# OpenSegment-v13.net
KiCad netlist of a schematic drawn in EAGLE
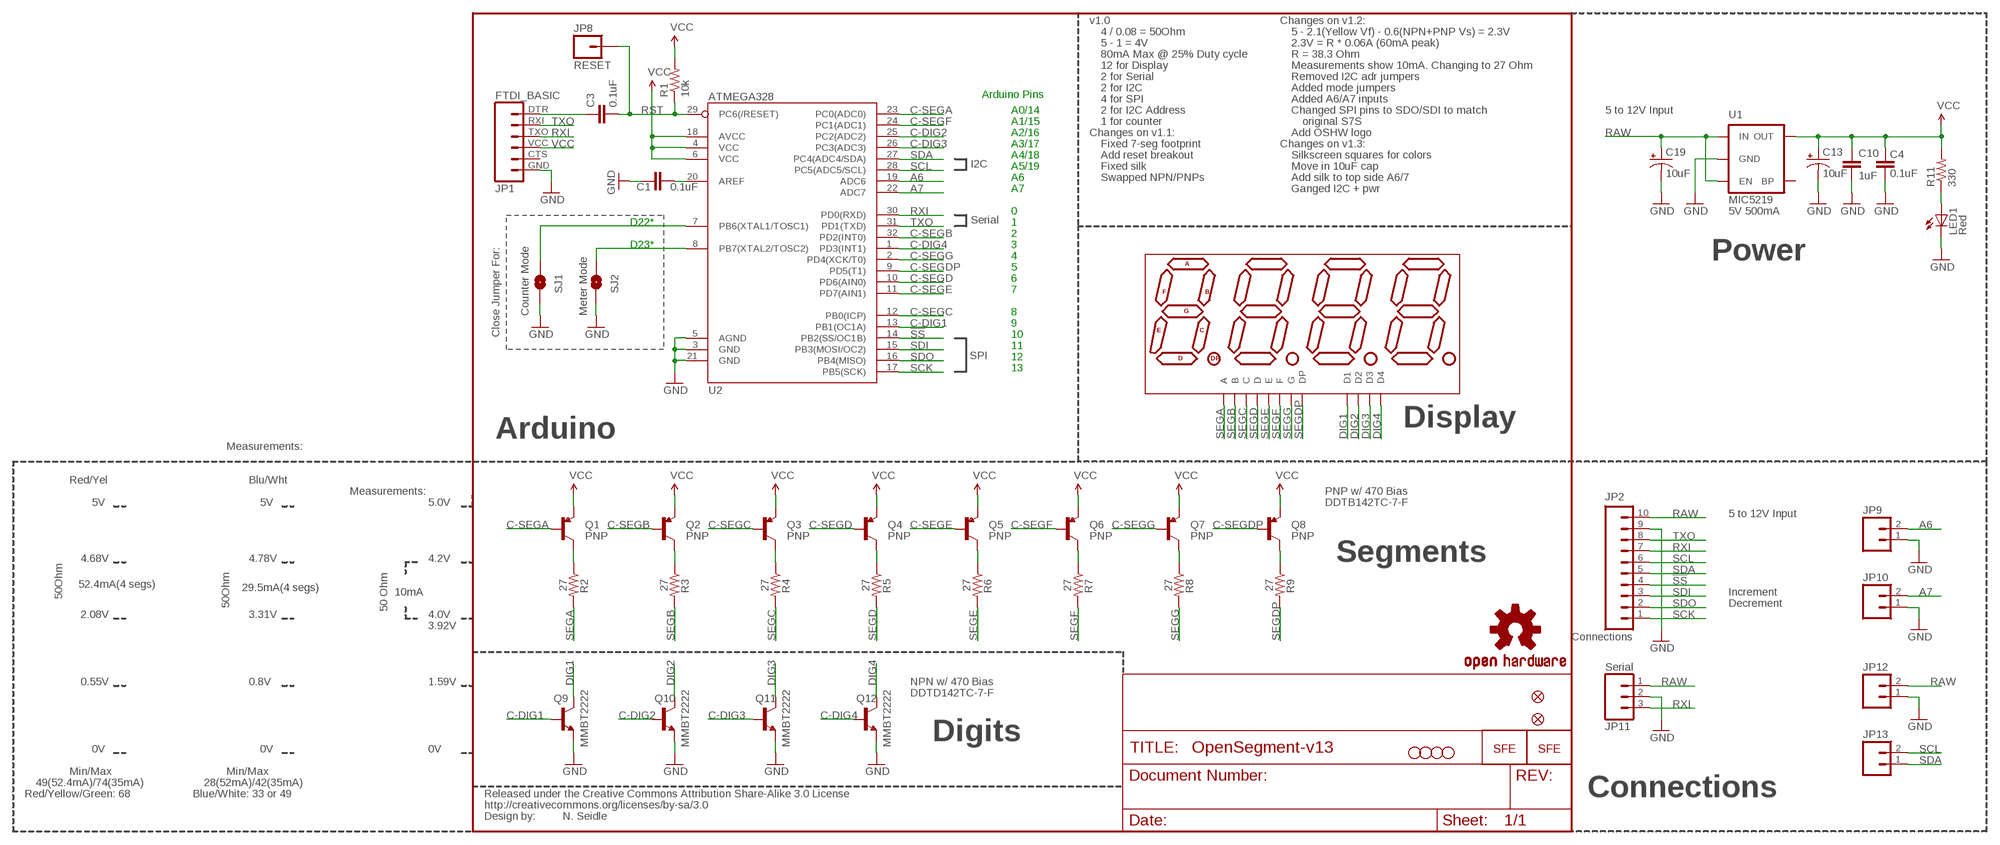
[diagram p0: schematic, sheet 1]

(export (version "E")
  (design (tool "Eeschema 10.0.6"))
  (components
    (comp (ref "C1")
      (value "0.1uF")
      (footprint "eagle-import:0402-CAP")
      (libsource (lib "eagle-import") (part "CAP0402-CAP"))
    )
    (comp (ref "C3")
      (value "0.1uF")
      (footprint "eagle-import:0402-CAP")
      (libsource (lib "eagle-import") (part "CAP0402-CAP"))
    )
    (comp (ref "C4")
      (value "0.1uF")
      (footprint "eagle-import:0402-CAP")
      (libsource (lib "eagle-import") (part "CAP0402-CAP"))
    )
    (comp (ref "C10")
      (value "1uF")
      (footprint "eagle-import:0402-CAP")
      (libsource (lib "eagle-import") (part "CAP0402-CAP"))
    )
    (comp (ref "C13")
      (value "10uF")
      (footprint "eagle-import:EIA3216")
      (libsource (lib "eagle-import") (part "CAP_POL1206"))
    )
    (comp (ref "C19")
      (value "10uF")
      (footprint "eagle-import:EIA3216")
      (libsource (lib "eagle-import") (part "CAP_POL1206"))
    )
    (comp (ref "JP1")
      (value "FTDI_BASIC")
      (footprint "eagle-import:FTDI_BASIC")
      (libsource (lib "eagle-import") (part "FTDI_BASICPTH"))
    )
    (comp (ref "JP2")
      (value "Connections")
      (footprint "eagle-import:1X10")
      (libsource (lib "eagle-import") (part "M10{dblquote}"))
    )
    (comp (ref "JP3")
      (value "STAND-OFF")
      (footprint "eagle-import:STAND-OFF")
      (libsource (lib "eagle-import") (part "STAND-OFF"))
    )
    (comp (ref "JP4")
      (value "STAND-OFF")
      (footprint "eagle-import:STAND-OFF")
      (libsource (lib "eagle-import") (part "STAND-OFF"))
    )
    (comp (ref "JP5")
      (value "STAND-OFF")
      (footprint "eagle-import:STAND-OFF")
      (libsource (lib "eagle-import") (part "STAND-OFF"))
    )
    (comp (ref "JP6")
      (value "STAND-OFF")
      (footprint "eagle-import:STAND-OFF")
      (libsource (lib "eagle-import") (part "STAND-OFF"))
    )
    (comp (ref "JP7")
      (value "FIDUCIALUFIDUCIAL")
      (footprint "eagle-import:MICRO-FIDUCIAL")
      (libsource (lib "eagle-import") (part "FIDUCIALUFIDUCIAL"))
    )
    (comp (ref "JP8")
      (value "RESET")
      (footprint "eagle-import:1X01")
      (libsource (lib "eagle-import") (part "M01PTH"))
    )
    (comp (ref "JP9")
      (value "M02PTH")
      (footprint "eagle-import:1X02")
      (libsource (lib "eagle-import") (part "M02PTH"))
    )
    (comp (ref "JP10")
      (value "M02PTH")
      (footprint "eagle-import:1X02")
      (libsource (lib "eagle-import") (part "M02PTH"))
    )
    (comp (ref "JP11")
      (value "Serial")
      (footprint "eagle-import:JST-3-PTH")
      (libsource (lib "eagle-import") (part "M03JST-PTH"))
    )
    (comp (ref "JP12")
      (value "M02PTH")
      (footprint "eagle-import:1X02")
      (libsource (lib "eagle-import") (part "M02PTH"))
    )
    (comp (ref "JP13")
      (value "M02PTH")
      (footprint "eagle-import:1X02")
      (libsource (lib "eagle-import") (part "M02PTH"))
    )
    (comp (ref "JP14")
      (value "FIDUCIALUFIDUCIAL")
      (footprint "eagle-import:MICRO-FIDUCIAL")
      (libsource (lib "eagle-import") (part "FIDUCIALUFIDUCIAL"))
    )
    (comp (ref "LED1")
      (value "Red")
      (footprint "eagle-import:LED-0603")
      (libsource (lib "eagle-import") (part "LED0603"))
    )
    (comp (ref "Q1")
      (value "PNP")
      (footprint "eagle-import:SOT23-3")
      (libsource (lib "eagle-import") (part "TRANSISTOR_PNPSMD"))
    )
    (comp (ref "Q2")
      (value "PNP")
      (footprint "eagle-import:SOT23-3")
      (libsource (lib "eagle-import") (part "TRANSISTOR_PNPSMD"))
    )
    (comp (ref "Q3")
      (value "PNP")
      (footprint "eagle-import:SOT23-3")
      (libsource (lib "eagle-import") (part "TRANSISTOR_PNPSMD"))
    )
    (comp (ref "Q4")
      (value "PNP")
      (footprint "eagle-import:SOT23-3")
      (libsource (lib "eagle-import") (part "TRANSISTOR_PNPSMD"))
    )
    (comp (ref "Q5")
      (value "PNP")
      (footprint "eagle-import:SOT23-3")
      (libsource (lib "eagle-import") (part "TRANSISTOR_PNPSMD"))
    )
    (comp (ref "Q6")
      (value "PNP")
      (footprint "eagle-import:SOT23-3")
      (libsource (lib "eagle-import") (part "TRANSISTOR_PNPSMD"))
    )
    (comp (ref "Q7")
      (value "PNP")
      (footprint "eagle-import:SOT23-3")
      (libsource (lib "eagle-import") (part "TRANSISTOR_PNPSMD"))
    )
    (comp (ref "Q8")
      (value "PNP")
      (footprint "eagle-import:SOT23-3")
      (libsource (lib "eagle-import") (part "TRANSISTOR_PNPSMD"))
    )
    (comp (ref "Q9")
      (value "MMBT2222")
      (footprint "eagle-import:SOT23-3")
      (libsource (lib "eagle-import") (part "TRANSISTOR_NPNSOT23-3"))
    )
    (comp (ref "Q10")
      (value "MMBT2222")
      (footprint "eagle-import:SOT23-3")
      (libsource (lib "eagle-import") (part "TRANSISTOR_NPNSOT23-3"))
    )
    (comp (ref "Q11")
      (value "MMBT2222")
      (footprint "eagle-import:SOT23-3")
      (libsource (lib "eagle-import") (part "TRANSISTOR_NPNSOT23-3"))
    )
    (comp (ref "Q12")
      (value "MMBT2222")
      (footprint "eagle-import:SOT23-3")
      (libsource (lib "eagle-import") (part "TRANSISTOR_NPNSOT23-3"))
    )
    (comp (ref "R1")
      (value "10k")
      (footprint "eagle-import:0402-RES")
      (libsource (lib "eagle-import") (part "RESISTOR0402-RES"))
    )
    (comp (ref "R2")
      (value "27")
      (footprint "eagle-import:0402-RES")
      (libsource (lib "eagle-import") (part "RESISTOR0402-RES"))
    )
    (comp (ref "R3")
      (value "27")
      (footprint "eagle-import:0402-RES")
      (libsource (lib "eagle-import") (part "RESISTOR0402-RES"))
    )
    (comp (ref "R4")
      (value "27")
      (footprint "eagle-import:0402-RES")
      (libsource (lib "eagle-import") (part "RESISTOR0402-RES"))
    )
    (comp (ref "R5")
      (value "27")
      (footprint "eagle-import:0402-RES")
      (libsource (lib "eagle-import") (part "RESISTOR0402-RES"))
    )
    (comp (ref "R6")
      (value "27")
      (footprint "eagle-import:0402-RES")
      (libsource (lib "eagle-import") (part "RESISTOR0402-RES"))
    )
    (comp (ref "R7")
      (value "27")
      (footprint "eagle-import:0402-RES")
      (libsource (lib "eagle-import") (part "RESISTOR0402-RES"))
    )
    (comp (ref "R8")
      (value "27")
      (footprint "eagle-import:0402-RES")
      (libsource (lib "eagle-import") (part "RESISTOR0402-RES"))
    )
    (comp (ref "R9")
      (value "27")
      (footprint "eagle-import:0402-RES")
      (libsource (lib "eagle-import") (part "RESISTOR0402-RES"))
    )
    (comp (ref "R11")
      (value "330")
      (footprint "eagle-import:0402-RES")
      (libsource (lib "eagle-import") (part "RESISTOR0402-RES"))
    )
    (comp (ref "SJ1")
      (value "Counter Ctl")
      (footprint "eagle-import:SJ_2S-NO")
      (libsource (lib "eagle-import") (part "SOLDERJUMPERNO"))
    )
    (comp (ref "SJ2")
      (value "Counter Ctl")
      (footprint "eagle-import:SJ_2S-NO")
      (libsource (lib "eagle-import") (part "SOLDERJUMPERNO"))
    )
    (comp (ref "U$2")
      (value "LOGO-SFESK")
      (footprint "eagle-import:SFE-LOGO-FLAME")
      (libsource (lib "eagle-import") (part "LOGO-SFESK"))
    )
    (comp (ref "U$3")
      (value "CREATIVE_COMMONS")
      (footprint "eagle-import:CREATIVE_COMMONS")
      (libsource (lib "eagle-import") (part "CREATIVE_COMMONS"))
    )
    (comp (ref "U$4")
      (value "OSHW-LOGOS")
      (footprint "eagle-import:OSHW-LOGO-S")
      (libsource (lib "eagle-import") (part "OSHW-LOGOS"))
    )
    (comp (ref "U$7")
      (value "LOGO-SFENW2")
      (footprint "eagle-import:SFE-NEW-WEB")
      (libsource (lib "eagle-import") (part "LOGO-SFENW2"))
    )
    (comp (ref "U1")
      (value "MIC5219")
      (footprint "eagle-import:SOT23-5")
      (libsource (lib "eagle-import") (part "V_REG_LDOSMD"))
    )
    (comp (ref "U2")
      (value "ATMEGA328")
      (footprint "eagle-import:TQFP32-08")
      (libsource (lib "eagle-import") (part "ATMEGA168"))
    )
    (comp (ref "U3")
      (value "7-SEGMENT-4DIGIT-COUNTERPTH")
      (footprint "eagle-import:7-SEGMENT-4DIGIT-COUNTER")
      (libsource (lib "eagle-import") (part "7-SEGMENT-4DIGIT-COUNTERPTH"))
    )
  )
  (nets
    (net (code "1") (name "/A6") (class "Default")
      (node (ref "JP9") (pin "2") (pinfunction "2_2") (pintype "passive"))
      (node (ref "U2") (pin "19") (pinfunction "ADC6_19") (pintype "bidirectional"))
    )
    (net (code "2") (name "/A7") (class "Default")
      (node (ref "JP10") (pin "2") (pinfunction "2_2") (pintype "passive"))
      (node (ref "U2") (pin "22") (pinfunction "ADC7_22") (pintype "bidirectional"))
    )
    (net (code "3") (name "/C-DIG1") (class "Default")
      (node (ref "Q9") (pin "1") (pinfunction "B_1") (pintype "passive"))
      (node (ref "U2") (pin "13") (pinfunction "PB1(OC1A)_13") (pintype "bidirectional"))
    )
    (net (code "4") (name "/C-DIG2") (class "Default")
      (node (ref "Q10") (pin "1") (pinfunction "B_1") (pintype "passive"))
      (node (ref "U2") (pin "25") (pinfunction "PC2(ADC2)_25") (pintype "bidirectional"))
    )
    (net (code "5") (name "/C-DIG3") (class "Default")
      (node (ref "Q11") (pin "1") (pinfunction "B_1") (pintype "passive"))
      (node (ref "U2") (pin "26") (pinfunction "PC3(ADC3)_26") (pintype "bidirectional"))
    )
    (net (code "6") (name "/C-DIG4") (class "Default")
      (node (ref "Q12") (pin "1") (pinfunction "B_1") (pintype "passive"))
      (node (ref "U2") (pin "1") (pinfunction "PD3(INT1)_1") (pintype "bidirectional"))
    )
    (net (code "7") (name "/C-SEGA") (class "Default")
      (node (ref "Q1") (pin "1") (pinfunction "B_1") (pintype "passive"))
      (node (ref "U2") (pin "23") (pinfunction "PC0(ADC0)_23") (pintype "bidirectional"))
    )
    (net (code "8") (name "/C-SEGB") (class "Default")
      (node (ref "Q2") (pin "1") (pinfunction "B_1") (pintype "passive"))
      (node (ref "U2") (pin "32") (pinfunction "PD2(INT0)_32") (pintype "bidirectional"))
    )
    (net (code "9") (name "/C-SEGC") (class "Default")
      (node (ref "Q3") (pin "1") (pinfunction "B_1") (pintype "passive"))
      (node (ref "U2") (pin "12") (pinfunction "PB0(ICP)_12") (pintype "bidirectional"))
    )
    (net (code "10") (name "/C-SEGD") (class "Default")
      (node (ref "Q4") (pin "1") (pinfunction "B_1") (pintype "passive"))
      (node (ref "U2") (pin "10") (pinfunction "PD6(AIN0)_10") (pintype "bidirectional"))
    )
    (net (code "11") (name "/C-SEGDP") (class "Default")
      (node (ref "Q8") (pin "1") (pinfunction "B_1") (pintype "passive"))
      (node (ref "U2") (pin "9") (pinfunction "PD5(T1)_9") (pintype "bidirectional"))
    )
    (net (code "12") (name "/C-SEGE") (class "Default")
      (node (ref "Q5") (pin "1") (pinfunction "B_1") (pintype "passive"))
      (node (ref "U2") (pin "11") (pinfunction "PD7(AIN1)_11") (pintype "bidirectional"))
    )
    (net (code "13") (name "/C-SEGF") (class "Default")
      (node (ref "Q6") (pin "1") (pinfunction "B_1") (pintype "passive"))
      (node (ref "U2") (pin "24") (pinfunction "PC1(ADC1)_24") (pintype "bidirectional"))
    )
    (net (code "14") (name "/C-SEGG") (class "Default")
      (node (ref "Q7") (pin "1") (pinfunction "B_1") (pintype "passive"))
      (node (ref "U2") (pin "2") (pinfunction "PD4(XCK/T0)_2") (pintype "bidirectional"))
    )
    (net (code "15") (name "/DIG1") (class "Default")
      (node (ref "Q9") (pin "3") (pinfunction "C_3") (pintype "passive"))
      (node (ref "U3") (pin "12") (pinfunction "D1_12") (pintype "bidirectional"))
    )
    (net (code "16") (name "/DIG2") (class "Default")
      (node (ref "Q10") (pin "3") (pinfunction "C_3") (pintype "passive"))
      (node (ref "U3") (pin "9") (pinfunction "D2_9") (pintype "bidirectional"))
    )
    (net (code "17") (name "/DIG3") (class "Default")
      (node (ref "Q11") (pin "3") (pinfunction "C_3") (pintype "passive"))
      (node (ref "U3") (pin "8") (pinfunction "D3_8") (pintype "bidirectional"))
    )
    (net (code "18") (name "/DIG4") (class "Default")
      (node (ref "Q12") (pin "3") (pinfunction "C_3") (pintype "passive"))
      (node (ref "U3") (pin "6") (pinfunction "D4_6") (pintype "bidirectional"))
    )
    (net (code "19") (name "/RAW") (class "Default")
      (node (ref "C19") (pin "A") (pinfunction "+_A") (pintype "passive"))
      (node (ref "JP11") (pin "1") (pinfunction "1_1") (pintype "passive"))
      (node (ref "JP12") (pin "2") (pinfunction "2_2") (pintype "passive"))
      (node (ref "JP2") (pin "10") (pinfunction "10_10") (pintype "passive"))
      (node (ref "U1") (pin "1") (pinfunction "IN_1") (pintype "input"))
      (node (ref "U1") (pin "3") (pinfunction "EN_3") (pintype "input"))
    )
    (net (code "20") (name "/RST") (class "Default")
      (node (ref "C3") (pin "2") (pinfunction "2_2") (pintype "passive"))
      (node (ref "JP8") (pin "1") (pinfunction "1_1") (pintype "passive"))
      (node (ref "R1") (pin "1") (pinfunction "1_1") (pintype "passive"))
      (node (ref "U2") (pin "29") (pinfunction "PC6(/RESET)_29") (pintype "bidirectional"))
    )
    (net (code "21") (name "/RXI") (class "Default")
      (node (ref "JP1") (pin "TXO") (pinfunction "3_TXO") (pintype "passive"))
      (node (ref "JP11") (pin "3") (pinfunction "3_3") (pintype "passive"))
      (node (ref "JP2") (pin "7") (pinfunction "7_7") (pintype "passive"))
      (node (ref "U2") (pin "30") (pinfunction "PD0(RXD)_30") (pintype "bidirectional"))
    )
    (net (code "22") (name "/SCK") (class "Default")
      (node (ref "JP2") (pin "1") (pinfunction "1_1") (pintype "passive"))
      (node (ref "U2") (pin "17") (pinfunction "PB5(SCK)_17") (pintype "bidirectional"))
    )
    (net (code "23") (name "/SCL") (class "Default")
      (node (ref "JP13") (pin "2") (pinfunction "2_2") (pintype "passive"))
      (node (ref "JP2") (pin "6") (pinfunction "6_6") (pintype "passive"))
      (node (ref "U2") (pin "28") (pinfunction "PC5(ADC5/SCL)_28") (pintype "bidirectional"))
    )
    (net (code "24") (name "/SDA") (class "Default")
      (node (ref "JP13") (pin "1") (pinfunction "1_1") (pintype "passive"))
      (node (ref "JP2") (pin "5") (pinfunction "5_5") (pintype "passive"))
      (node (ref "U2") (pin "27") (pinfunction "PC4(ADC4/SDA)_27") (pintype "bidirectional"))
    )
    (net (code "25") (name "/SDI") (class "Default")
      (node (ref "JP2") (pin "3") (pinfunction "3_3") (pintype "passive"))
      (node (ref "U2") (pin "15") (pinfunction "PB3(MOSI/OC2)_15") (pintype "bidirectional"))
    )
    (net (code "26") (name "/SDO") (class "Default")
      (node (ref "JP2") (pin "2") (pinfunction "2_2") (pintype "passive"))
      (node (ref "U2") (pin "16") (pinfunction "PB4(MISO)_16") (pintype "bidirectional"))
    )
    (net (code "27") (name "/SEGA") (class "Default")
      (node (ref "R2") (pin "2") (pinfunction "2_2") (pintype "passive"))
      (node (ref "U3") (pin "11") (pinfunction "A_11") (pintype "bidirectional"))
    )
    (net (code "28") (name "/SEGB") (class "Default")
      (node (ref "R3") (pin "2") (pinfunction "2_2") (pintype "passive"))
      (node (ref "U3") (pin "7") (pinfunction "B_7") (pintype "bidirectional"))
    )
    (net (code "29") (name "/SEGC") (class "Default")
      (node (ref "R4") (pin "2") (pinfunction "2_2") (pintype "passive"))
      (node (ref "U3") (pin "4") (pinfunction "C_4") (pintype "bidirectional"))
    )
    (net (code "30") (name "/SEGD") (class "Default")
      (node (ref "R5") (pin "2") (pinfunction "2_2") (pintype "passive"))
      (node (ref "U3") (pin "2") (pinfunction "D_2") (pintype "bidirectional"))
    )
    (net (code "31") (name "/SEGDP") (class "Default")
      (node (ref "R9") (pin "2") (pinfunction "2_2") (pintype "passive"))
      (node (ref "U3") (pin "3") (pinfunction "DP_3") (pintype "bidirectional"))
    )
    (net (code "32") (name "/SEGE") (class "Default")
      (node (ref "R6") (pin "2") (pinfunction "2_2") (pintype "passive"))
      (node (ref "U3") (pin "1") (pinfunction "E_1") (pintype "bidirectional"))
    )
    (net (code "33") (name "/SEGF") (class "Default")
      (node (ref "R7") (pin "2") (pinfunction "2_2") (pintype "passive"))
      (node (ref "U3") (pin "10") (pinfunction "F_10") (pintype "bidirectional"))
    )
    (net (code "34") (name "/SEGG") (class "Default")
      (node (ref "R8") (pin "2") (pinfunction "2_2") (pintype "passive"))
      (node (ref "U3") (pin "5") (pinfunction "G_5") (pintype "bidirectional"))
    )
    (net (code "35") (name "/TXO") (class "Default")
      (node (ref "JP1") (pin "RXI") (pinfunction "2_RXI") (pintype "passive"))
      (node (ref "JP2") (pin "8") (pinfunction "8_8") (pintype "passive"))
      (node (ref "U2") (pin "31") (pinfunction "PD1(TXD)_31") (pintype "bidirectional"))
    )
    (net (code "36") (name "/~{SS}") (class "Default")
      (node (ref "JP2") (pin "4") (pinfunction "4_4") (pintype "passive"))
      (node (ref "U2") (pin "14") (pinfunction "PB2(SS/OC1B)_14") (pintype "bidirectional"))
    )
    (net (code "37") (name "GND") (class "Default")
      (node (ref "C1") (pin "1") (pinfunction "1_1") (pintype "passive"))
      (node (ref "C10") (pin "2") (pinfunction "2_2") (pintype "passive"))
      (node (ref "C13") (pin "C") (pinfunction "-_C") (pintype "passive"))
      (node (ref "C19") (pin "C") (pinfunction "-_C") (pintype "passive"))
      (node (ref "C4") (pin "1") (pinfunction "1_1") (pintype "passive"))
      (node (ref "JP1") (pin "GND") (pinfunction "6_GND") (pintype "passive"))
      (node (ref "JP10") (pin "1") (pinfunction "1_1") (pintype "passive"))
      (node (ref "JP11") (pin "2") (pinfunction "2_2") (pintype "passive"))
      (node (ref "JP12") (pin "1") (pinfunction "1_1") (pintype "passive"))
      (node (ref "JP2") (pin "9") (pinfunction "9_9") (pintype "passive"))
      (node (ref "JP9") (pin "1") (pinfunction "1_1") (pintype "passive"))
      (node (ref "LED1") (pin "C") (pinfunction "C_C") (pintype "passive"))
      (node (ref "Q10") (pin "2") (pinfunction "E_2") (pintype "passive"))
      (node (ref "Q11") (pin "2") (pinfunction "E_2") (pintype "passive"))
      (node (ref "Q12") (pin "2") (pinfunction "E_2") (pintype "passive"))
      (node (ref "Q9") (pin "2") (pinfunction "E_2") (pintype "passive"))
      (node (ref "SJ1") (pin "2") (pinfunction "2_2") (pintype "passive"))
      (node (ref "SJ2") (pin "2") (pinfunction "2_2") (pintype "passive"))
      (node (ref "U1") (pin "2") (pinfunction "GND_2") (pintype "input"))
      (node (ref "U2") (pin "21") (pinfunction "GND_21") (pintype "bidirectional"))
      (node (ref "U2") (pin "3") (pinfunction "GND_3") (pintype "bidirectional"))
      (node (ref "U2") (pin "5") (pinfunction "AGND_5") (pintype "bidirectional"))
    )
    (net (code "38") (name "Net-(JP1-1)") (class "Default")
      (node (ref "C3") (pin "1") (pinfunction "1_1") (pintype "passive"))
      (node (ref "JP1") (pin "DTR") (pinfunction "1_DTR") (pintype "passive"))
    )
    (net (code "39") (name "Net-(LED1-PadA)") (class "Default")
      (node (ref "LED1") (pin "A") (pinfunction "A_A") (pintype "passive"))
      (node (ref "R11") (pin "1") (pinfunction "1_1") (pintype "passive"))
    )
    (net (code "40") (name "Net-(Q1-C)") (class "Default")
      (node (ref "Q1") (pin "3") (pinfunction "C_3") (pintype "passive"))
      (node (ref "R2") (pin "1") (pinfunction "1_1") (pintype "passive"))
    )
    (net (code "41") (name "Net-(Q2-C)") (class "Default")
      (node (ref "Q2") (pin "3") (pinfunction "C_3") (pintype "passive"))
      (node (ref "R3") (pin "1") (pinfunction "1_1") (pintype "passive"))
    )
    (net (code "42") (name "Net-(Q3-C)") (class "Default")
      (node (ref "Q3") (pin "3") (pinfunction "C_3") (pintype "passive"))
      (node (ref "R4") (pin "1") (pinfunction "1_1") (pintype "passive"))
    )
    (net (code "43") (name "Net-(Q4-C)") (class "Default")
      (node (ref "Q4") (pin "3") (pinfunction "C_3") (pintype "passive"))
      (node (ref "R5") (pin "1") (pinfunction "1_1") (pintype "passive"))
    )
    (net (code "44") (name "Net-(Q5-C)") (class "Default")
      (node (ref "Q5") (pin "3") (pinfunction "C_3") (pintype "passive"))
      (node (ref "R6") (pin "1") (pinfunction "1_1") (pintype "passive"))
    )
    (net (code "45") (name "Net-(Q6-C)") (class "Default")
      (node (ref "Q6") (pin "3") (pinfunction "C_3") (pintype "passive"))
      (node (ref "R7") (pin "1") (pinfunction "1_1") (pintype "passive"))
    )
    (net (code "46") (name "Net-(Q7-C)") (class "Default")
      (node (ref "Q7") (pin "3") (pinfunction "C_3") (pintype "passive"))
      (node (ref "R8") (pin "1") (pinfunction "1_1") (pintype "passive"))
    )
    (net (code "47") (name "Net-(Q8-C)") (class "Default")
      (node (ref "Q8") (pin "3") (pinfunction "C_3") (pintype "passive"))
      (node (ref "R9") (pin "1") (pinfunction "1_1") (pintype "passive"))
    )
    (net (code "48") (name "Net-(U2-AREF)") (class "Default")
      (node (ref "C1") (pin "2") (pinfunction "2_2") (pintype "passive"))
      (node (ref "U2") (pin "20") (pinfunction "AREF_20") (pintype "bidirectional"))
    )
    (net (code "49") (name "Net-(U2-PB6(XTAL1{slash}TOSC1))") (class "Default")
      (node (ref "SJ1") (pin "1") (pinfunction "1_1") (pintype "passive"))
      (node (ref "U2") (pin "7") (pinfunction "PB6(XTAL1/TOSC1)_7") (pintype "bidirectional"))
    )
    (net (code "50") (name "Net-(U2-PB7(XTAL2{slash}TOSC2))") (class "Default")
      (node (ref "SJ2") (pin "1") (pinfunction "1_1") (pintype "passive"))
      (node (ref "U2") (pin "8") (pinfunction "PB7(XTAL2/TOSC2)_8") (pintype "bidirectional"))
    )
    (net (code "51") (name "VCC") (class "Default")
      (node (ref "C10") (pin "1") (pinfunction "1_1") (pintype "passive"))
      (node (ref "C13") (pin "A") (pinfunction "+_A") (pintype "passive"))
      (node (ref "C4") (pin "2") (pinfunction "2_2") (pintype "passive"))
      (node (ref "JP1") (pin "VCC") (pinfunction "4_VCC") (pintype "passive"))
      (node (ref "Q1") (pin "2") (pinfunction "E_2") (pintype "passive"))
      (node (ref "Q2") (pin "2") (pinfunction "E_2") (pintype "passive"))
      (node (ref "Q3") (pin "2") (pinfunction "E_2") (pintype "passive"))
      (node (ref "Q4") (pin "2") (pinfunction "E_2") (pintype "passive"))
      (node (ref "Q5") (pin "2") (pinfunction "E_2") (pintype "passive"))
      (node (ref "Q6") (pin "2") (pinfunction "E_2") (pintype "passive"))
      (node (ref "Q7") (pin "2") (pinfunction "E_2") (pintype "passive"))
      (node (ref "Q8") (pin "2") (pinfunction "E_2") (pintype "passive"))
      (node (ref "R1") (pin "2") (pinfunction "2_2") (pintype "passive"))
      (node (ref "R11") (pin "2") (pinfunction "2_2") (pintype "passive"))
      (node (ref "U1") (pin "5") (pinfunction "OUT_5") (pintype "passive"))
      (node (ref "U2") (pin "18") (pinfunction "AVCC_18") (pintype "bidirectional"))
      (node (ref "U2") (pin "4") (pinfunction "VCC_4") (pintype "bidirectional"))
      (node (ref "U2") (pin "6") (pinfunction "VCC_6") (pintype "bidirectional"))
    )
    (net (code "52") (name "unconnected-(JP1-5-PadCTS)") (class "Default")
      (node (ref "JP1") (pin "CTS") (pinfunction "5_CTS") (pintype "passive"))
    )
    (net (code "53") (name "unconnected-(U1-BP-Pad4)") (class "Default")
      (node (ref "U1") (pin "4") (pinfunction "BP_4") (pintype "input"))
    )
  )
)
